# FIT_HDMI_X27-23.net
KiCad netlist of a schematic drawn in Altium Designer
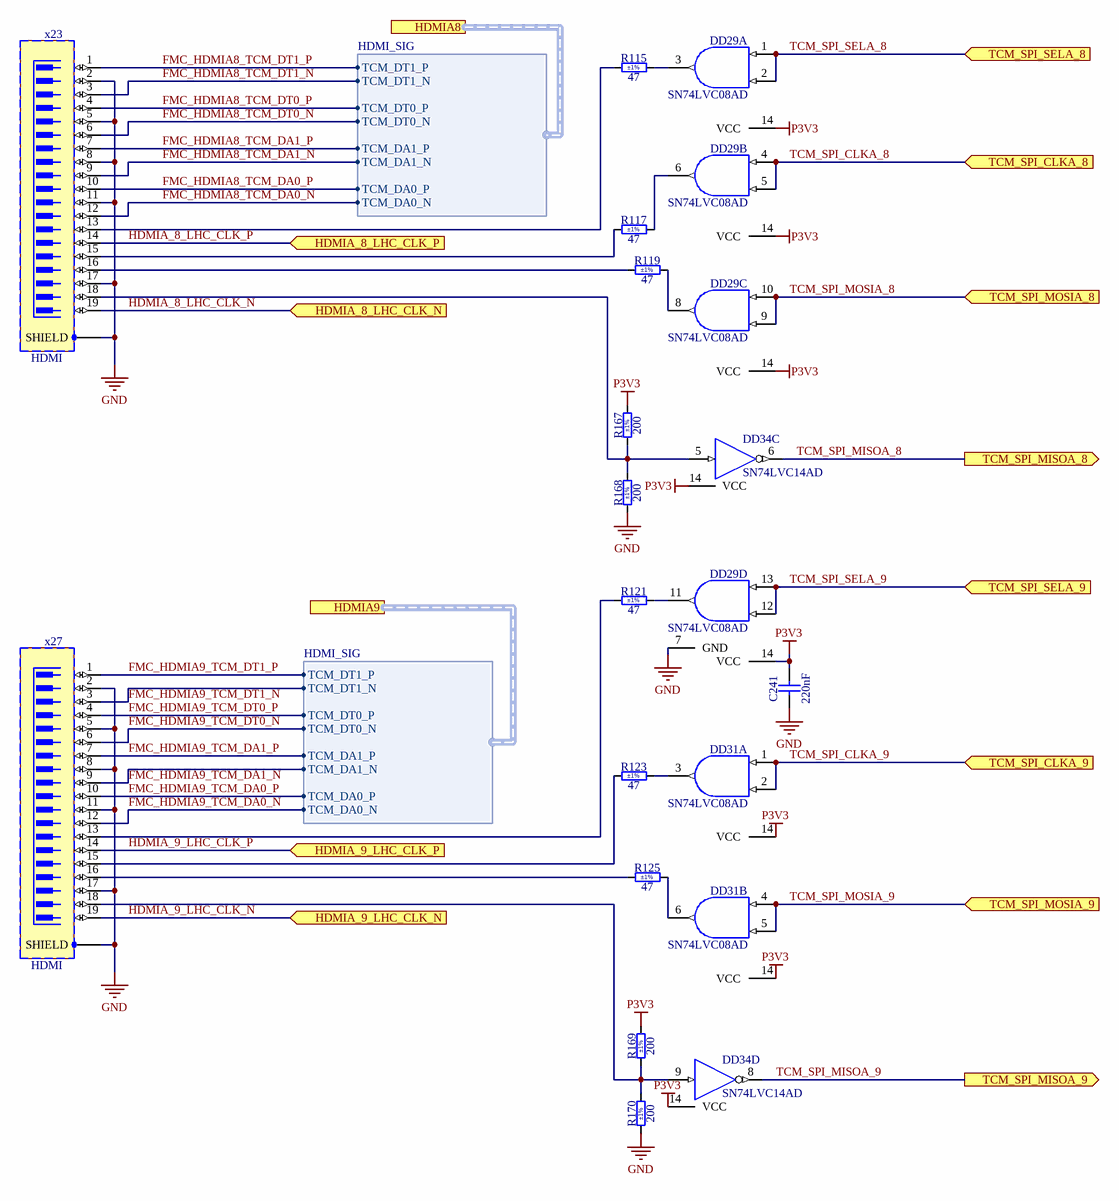
[diagram p0: FIT_HDMI_X27-23.SchDoc]

(export (version "E")
  (design (tool "Eeschema 10.0.6"))
  (components
    (comp (ref "C241")
      (value "220nF")
      (footprint "CAPC2012X135N")
      (description "Non-polarised capacitor")
      (fields
        (field (name "PART NUMBER") "CC0805_220NF_50V_10%_X7R")
        (field (name "VOLTAGE") "50V")
        (field (name "AUTHOR") "CERN DEM JLC")
      )
      (libsource (lib "Capacitors") (part "Capacitor - non polarized"))
    )
    (comp (ref "DD29")
      (value "SN74LVC08AD")
      (footprint "SOIC127P600X175-14N")
      (description "Quad 2-Input AND Gate")
      (fields (field (name "MANUFACTURER") "TEXAS INSTRUMENTS") (field (name "AUTHOR") "CERN DEM JLC"))
      (libsource (lib "ICs And Semiconductors") (part "7408"))
    )
    (comp (ref "DD31")
      (value "SN74LVC08AD")
      (footprint "SOIC127P600X175-14N")
      (description "Quad 2-Input AND Gate")
      (fields (field (name "MANUFACTURER") "TEXAS INSTRUMENTS") (field (name "AUTHOR") "CERN DEM JLC"))
      (libsource (lib "ICs And Semiconductors") (part "7408"))
    )
    (comp (ref "DD34")
      (value "SN74LVC14AD")
      (footprint "SOIC127P600X175-14N")
      (description "Hex Schmitt-Trigger Inverter")
      (fields (field (name "MANUFACTURER") "TEXAS INSTRUMENTS") (field (name "AUTHOR") "CERN DEM JMW"))
      (libsource (lib "ICs And Semiconductors") (part "7414"))
    )
    (comp (ref "R115")
      (value "47")
      (footprint "RESC2012X60N")
      (description "Resistor - 1%")
      (fields
        (field (name "TOLERANCE") "±1%")
        (field (name "PART NUMBER") "R0805_47R_1%_0.125W_100PPM")
        (field (name "POWER") "0.125W")
        (field (name "AUTHOR") "CERN DEM JLC")
      )
      (libsource (lib "Resistors") (part "Resistor - 1%"))
    )
    (comp (ref "R117")
      (value "47")
      (footprint "RESC2012X60N")
      (description "Resistor - 1%")
      (fields
        (field (name "TOLERANCE") "±1%")
        (field (name "PART NUMBER") "R0805_47R_1%_0.125W_100PPM")
        (field (name "POWER") "0.125W")
        (field (name "AUTHOR") "CERN DEM JLC")
      )
      (libsource (lib "Resistors") (part "Resistor - 1%"))
    )
    (comp (ref "R119")
      (value "47")
      (footprint "RESC2012X60N")
      (description "Resistor - 1%")
      (fields
        (field (name "TOLERANCE") "±1%")
        (field (name "PART NUMBER") "R0805_47R_1%_0.125W_100PPM")
        (field (name "POWER") "0.125W")
        (field (name "AUTHOR") "CERN DEM JLC")
      )
      (libsource (lib "Resistors") (part "Resistor - 1%"))
    )
    (comp (ref "R121")
      (value "47")
      (footprint "RESC2012X60N")
      (description "Resistor - 1%")
      (fields
        (field (name "TOLERANCE") "±1%")
        (field (name "PART NUMBER") "R0805_47R_1%_0.125W_100PPM")
        (field (name "POWER") "0.125W")
        (field (name "AUTHOR") "CERN DEM JLC")
      )
      (libsource (lib "Resistors") (part "Resistor - 1%"))
    )
    (comp (ref "R123")
      (value "47")
      (footprint "RESC2012X60N")
      (description "Resistor - 1%")
      (fields
        (field (name "TOLERANCE") "±1%")
        (field (name "PART NUMBER") "R0805_47R_1%_0.125W_100PPM")
        (field (name "POWER") "0.125W")
        (field (name "AUTHOR") "CERN DEM JLC")
      )
      (libsource (lib "Resistors") (part "Resistor - 1%"))
    )
    (comp (ref "R125")
      (value "47")
      (footprint "RESC2012X60N")
      (description "Resistor - 1%")
      (fields
        (field (name "TOLERANCE") "±1%")
        (field (name "PART NUMBER") "R0805_47R_1%_0.125W_100PPM")
        (field (name "POWER") "0.125W")
        (field (name "AUTHOR") "CERN DEM JLC")
      )
      (libsource (lib "Resistors") (part "Resistor - 1%"))
    )
    (comp (ref "R167")
      (value "200")
      (footprint "RESC2012X60N")
      (description "Resistor - 1%")
      (fields
        (field (name "TOLERANCE") "±1%")
        (field (name "PART NUMBER") "R0805_200R_1%_0.125W_100PPM")
        (field (name "POWER") "0.125W")
        (field (name "AUTHOR") "CERN DEM JLC")
      )
      (libsource (lib "Resistors") (part "Resistor - 1%"))
    )
    (comp (ref "R168")
      (value "200")
      (footprint "RESC2012X60N")
      (description "Resistor - 1%")
      (fields
        (field (name "TOLERANCE") "±1%")
        (field (name "PART NUMBER") "R0805_200R_1%_0.125W_100PPM")
        (field (name "POWER") "0.125W")
        (field (name "AUTHOR") "CERN DEM JLC")
      )
      (libsource (lib "Resistors") (part "Resistor - 1%"))
    )
    (comp (ref "R169")
      (value "200")
      (footprint "RESC2012X60N")
      (description "Resistor - 1%")
      (fields
        (field (name "TOLERANCE") "±1%")
        (field (name "PART NUMBER") "R0805_200R_1%_0.125W_100PPM")
        (field (name "POWER") "0.125W")
        (field (name "AUTHOR") "CERN DEM JLC")
      )
      (libsource (lib "Resistors") (part "Resistor - 1%"))
    )
    (comp (ref "R170")
      (value "200")
      (footprint "RESC2012X60N")
      (description "Resistor - 1%")
      (fields
        (field (name "TOLERANCE") "±1%")
        (field (name "PART NUMBER") "R0805_200R_1%_0.125W_100PPM")
        (field (name "POWER") "0.125W")
        (field (name "AUTHOR") "CERN DEM JLC")
      )
      (libsource (lib "Resistors") (part "Resistor - 1%"))
    )
    (comp (ref "x23")
      (value "HDMI")
      (footprint "TYCO_2007435-1")
      (description "Connector HDMI 19 Male + 1 Shield")
      (fields
        (field (name "PART NUMBER") "TYCO_2007435-1")
        (field (name "MANUFACTURER") "TYCO ELECTRONICS")
        (field (name "AUTHOR") "CERN DEM MR")
      )
      (libsource (lib "Connectors") (part "Connector HDMI 19 Male + 1 Shield"))
    )
    (comp (ref "x27")
      (value "HDMI")
      (footprint "TYCO_2007435-1")
      (description "Connector HDMI 19 Male + 1 Shield")
      (fields
        (field (name "PART NUMBER") "TYCO_2007435-1")
        (field (name "MANUFACTURER") "TYCO ELECTRONICS")
        (field (name "AUTHOR") "CERN DEM MR")
      )
      (libsource (lib "Connectors") (part "Connector HDMI 19 Male + 1 Shield"))
    )
  )
  (nets
    (net (code "2") (name "/FMC_HDMIA8_TCM_DA0_N") (class "Default")
      (node (ref "x23") (pin "12") (pinfunction "12_12") (pintype "bidirectional"))
    )
    (net (code "3") (name "/FMC_HDMIA8_TCM_DA0_P") (class "Default")
      (node (ref "x23") (pin "10") (pinfunction "10_10") (pintype "bidirectional"))
    )
    (net (code "4") (name "/FMC_HDMIA8_TCM_DA1_N") (class "Default")
      (node (ref "x23") (pin "9") (pinfunction "9_9") (pintype "bidirectional"))
    )
    (net (code "5") (name "/FMC_HDMIA8_TCM_DA1_P") (class "Default")
      (node (ref "x23") (pin "7") (pinfunction "7_7") (pintype "bidirectional"))
    )
    (net (code "6") (name "/FMC_HDMIA8_TCM_DT0_N") (class "Default")
      (node (ref "x23") (pin "6") (pinfunction "6_6") (pintype "bidirectional"))
    )
    (net (code "7") (name "/FMC_HDMIA8_TCM_DT0_P") (class "Default")
      (node (ref "x23") (pin "4") (pinfunction "4_4") (pintype "bidirectional"))
    )
    (net (code "8") (name "/FMC_HDMIA8_TCM_DT1_N") (class "Default")
      (node (ref "x23") (pin "3") (pinfunction "3_3") (pintype "bidirectional"))
    )
    (net (code "9") (name "/FMC_HDMIA8_TCM_DT1_P") (class "Default")
      (node (ref "x23") (pin "1") (pinfunction "1_1") (pintype "bidirectional"))
    )
    (net (code "10") (name "/FMC_HDMIA9_TCM_DA0_N") (class "Default")
      (node (ref "x27") (pin "12") (pinfunction "12_12") (pintype "bidirectional"))
    )
    (net (code "11") (name "/FMC_HDMIA9_TCM_DA0_P") (class "Default")
      (node (ref "x27") (pin "10") (pinfunction "10_10") (pintype "bidirectional"))
    )
    (net (code "12") (name "/FMC_HDMIA9_TCM_DA1_N") (class "Default")
      (node (ref "x27") (pin "9") (pinfunction "9_9") (pintype "bidirectional"))
    )
    (net (code "13") (name "/FMC_HDMIA9_TCM_DA1_P") (class "Default")
      (node (ref "x27") (pin "7") (pinfunction "7_7") (pintype "bidirectional"))
    )
    (net (code "14") (name "/FMC_HDMIA9_TCM_DT0_N") (class "Default")
      (node (ref "x27") (pin "6") (pinfunction "6_6") (pintype "bidirectional"))
    )
    (net (code "15") (name "/FMC_HDMIA9_TCM_DT0_P") (class "Default")
      (node (ref "x27") (pin "4") (pinfunction "4_4") (pintype "bidirectional"))
    )
    (net (code "16") (name "/FMC_HDMIA9_TCM_DT1_N") (class "Default")
      (node (ref "x27") (pin "3") (pinfunction "3_3") (pintype "bidirectional"))
    )
    (net (code "17") (name "/FMC_HDMIA9_TCM_DT1_P") (class "Default")
      (node (ref "x27") (pin "1") (pinfunction "1_1") (pintype "bidirectional"))
    )
    (net (code "18") (name "/HDMIA_8_LHC_CLK_N") (class "Default")
      (node (ref "x23") (pin "19") (pinfunction "19_19") (pintype "bidirectional"))
    )
    (net (code "19") (name "/HDMIA_8_LHC_CLK_P") (class "Default")
      (node (ref "x23") (pin "14") (pinfunction "14_14") (pintype "bidirectional"))
    )
    (net (code "20") (name "/HDMIA_9_LHC_CLK_N") (class "Default")
      (node (ref "x27") (pin "19") (pinfunction "19_19") (pintype "bidirectional"))
    )
    (net (code "21") (name "/HDMIA_9_LHC_CLK_P") (class "Default")
      (node (ref "x27") (pin "14") (pinfunction "14_14") (pintype "bidirectional"))
    )
    (net (code "22") (name "/TCM_SPI_CLKA_8") (class "Default")
      (node (ref "DD29") (pin "4") (pinfunction "A_4") (pintype "input"))
      (node (ref "DD29") (pin "5") (pinfunction "B_5") (pintype "input"))
    )
    (net (code "23") (name "/TCM_SPI_CLKA_9") (class "Default")
      (node (ref "DD31") (pin "1") (pinfunction "A_1") (pintype "input"))
      (node (ref "DD31") (pin "2") (pinfunction "B_2") (pintype "input"))
    )
    (net (code "24") (name "/TCM_SPI_MISOA_8") (class "Default")
      (node (ref "DD34") (pin "6") (pinfunction "OUT_6") (pintype "output"))
    )
    (net (code "25") (name "/TCM_SPI_MISOA_9") (class "Default")
      (node (ref "DD34") (pin "8") (pinfunction "OUT_8") (pintype "output"))
    )
    (net (code "26") (name "/TCM_SPI_MOSIA_8") (class "Default")
      (node (ref "DD29") (pin "10") (pinfunction "A_10") (pintype "input"))
      (node (ref "DD29") (pin "9") (pinfunction "B_9") (pintype "input"))
    )
    (net (code "27") (name "/TCM_SPI_MOSIA_9") (class "Default")
      (node (ref "DD31") (pin "4") (pinfunction "A_4") (pintype "input"))
      (node (ref "DD31") (pin "5") (pinfunction "B_5") (pintype "input"))
    )
    (net (code "28") (name "/TCM_SPI_SELA_8") (class "Default")
      (node (ref "DD29") (pin "1") (pinfunction "A_1") (pintype "input"))
      (node (ref "DD29") (pin "2") (pinfunction "B_2") (pintype "input"))
    )
    (net (code "29") (name "/TCM_SPI_SELA_9") (class "Default")
      (node (ref "DD29") (pin "12") (pinfunction "B_12") (pintype "input"))
      (node (ref "DD29") (pin "13") (pinfunction "A_13") (pintype "input"))
    )
    (net (code "31") (name "GND") (class "Default")
      (node (ref "C241") (pin "1") (pinfunction "1_1") (pintype "passive"))
      (node (ref "DD29") (pin "7") (pinfunction "GND_7") (pintype "power_in"))
      (node (ref "DD31") (pin "7") (pinfunction "GND_7") (pintype "power_in"))
      (node (ref "DD34") (pin "7") (pinfunction "GND_7") (pintype "power_in"))
      (node (ref "R168") (pin "1") (pinfunction "1_1") (pintype "passive"))
      (node (ref "R170") (pin "1") (pinfunction "1_1") (pintype "passive"))
      (node (ref "x23") (pin "11") (pinfunction "11_11") (pintype "bidirectional"))
      (node (ref "x23") (pin "17") (pinfunction "17_17") (pintype "bidirectional"))
      (node (ref "x23") (pin "2") (pinfunction "2_2") (pintype "bidirectional"))
      (node (ref "x23") (pin "5") (pinfunction "5_5") (pintype "bidirectional"))
      (node (ref "x23") (pin "8") (pinfunction "8_8") (pintype "bidirectional"))
      (node (ref "x23") (pin "SHIELD") (pinfunction "SHIELD_SHIELD") (pintype "power_in"))
      (node (ref "x27") (pin "11") (pinfunction "11_11") (pintype "bidirectional"))
      (node (ref "x27") (pin "17") (pinfunction "17_17") (pintype "bidirectional"))
      (node (ref "x27") (pin "2") (pinfunction "2_2") (pintype "bidirectional"))
      (node (ref "x27") (pin "5") (pinfunction "5_5") (pintype "bidirectional"))
      (node (ref "x27") (pin "8") (pinfunction "8_8") (pintype "bidirectional"))
      (node (ref "x27") (pin "SHIELD") (pinfunction "SHIELD_SHIELD") (pintype "power_in"))
    )
    (net (code "32") (name "Net-(DD29A-Y)") (class "Default")
      (node (ref "DD29") (pin "3") (pinfunction "Y_3") (pintype "output"))
      (node (ref "R115") (pin "2") (pinfunction "2_2") (pintype "passive"))
    )
    (net (code "33") (name "Net-(DD29B-Y)") (class "Default")
      (node (ref "DD29") (pin "6") (pinfunction "Y_6") (pintype "output"))
      (node (ref "R117") (pin "2") (pinfunction "2_2") (pintype "passive"))
    )
    (net (code "34") (name "Net-(DD29C-Y)") (class "Default")
      (node (ref "DD29") (pin "8") (pinfunction "Y_8") (pintype "output"))
      (node (ref "R119") (pin "2") (pinfunction "2_2") (pintype "passive"))
    )
    (net (code "35") (name "Net-(DD29D-Y)") (class "Default")
      (node (ref "DD29") (pin "11") (pinfunction "Y_11") (pintype "output"))
      (node (ref "R121") (pin "2") (pinfunction "2_2") (pintype "passive"))
    )
    (net (code "36") (name "Net-(DD31A-Y)") (class "Default")
      (node (ref "DD31") (pin "3") (pinfunction "Y_3") (pintype "output"))
      (node (ref "R123") (pin "2") (pinfunction "2_2") (pintype "passive"))
    )
    (net (code "37") (name "Net-(DD31B-Y)") (class "Default")
      (node (ref "DD31") (pin "6") (pinfunction "Y_6") (pintype "output"))
      (node (ref "R125") (pin "2") (pinfunction "2_2") (pintype "passive"))
    )
    (net (code "38") (name "Net-(DD34C-IN)") (class "Default")
      (node (ref "DD34") (pin "5") (pinfunction "IN_5") (pintype "input"))
      (node (ref "R167") (pin "1") (pinfunction "1_1") (pintype "passive"))
      (node (ref "R168") (pin "2") (pinfunction "2_2") (pintype "passive"))
      (node (ref "x23") (pin "18") (pinfunction "18_18") (pintype "bidirectional"))
    )
    (net (code "39") (name "Net-(DD34D-IN)") (class "Default")
      (node (ref "DD34") (pin "9") (pinfunction "IN_9") (pintype "input"))
      (node (ref "R169") (pin "1") (pinfunction "1_1") (pintype "passive"))
      (node (ref "R170") (pin "2") (pinfunction "2_2") (pintype "passive"))
      (node (ref "x27") (pin "18") (pinfunction "18_18") (pintype "bidirectional"))
    )
    (net (code "40") (name "Net-(R115-Pad1)") (class "Default")
      (node (ref "R115") (pin "1") (pinfunction "1_1") (pintype "passive"))
      (node (ref "x23") (pin "13") (pinfunction "13_13") (pintype "bidirectional"))
    )
    (net (code "41") (name "Net-(R117-Pad1)") (class "Default")
      (node (ref "R117") (pin "1") (pinfunction "1_1") (pintype "passive"))
      (node (ref "x23") (pin "15") (pinfunction "15_15") (pintype "bidirectional"))
    )
    (net (code "42") (name "Net-(R119-Pad1)") (class "Default")
      (node (ref "R119") (pin "1") (pinfunction "1_1") (pintype "passive"))
      (node (ref "x23") (pin "16") (pinfunction "16_16") (pintype "bidirectional"))
    )
    (net (code "43") (name "Net-(R121-Pad1)") (class "Default")
      (node (ref "R121") (pin "1") (pinfunction "1_1") (pintype "passive"))
      (node (ref "x27") (pin "13") (pinfunction "13_13") (pintype "bidirectional"))
    )
    (net (code "44") (name "Net-(R123-Pad1)") (class "Default")
      (node (ref "R123") (pin "1") (pinfunction "1_1") (pintype "passive"))
      (node (ref "x27") (pin "15") (pinfunction "15_15") (pintype "bidirectional"))
    )
    (net (code "45") (name "Net-(R125-Pad1)") (class "Default")
      (node (ref "R125") (pin "1") (pinfunction "1_1") (pintype "passive"))
      (node (ref "x27") (pin "16") (pinfunction "16_16") (pintype "bidirectional"))
    )
    (net (code "46") (name "P3V3") (class "Default")
      (node (ref "C241") (pin "2") (pinfunction "2_2") (pintype "passive"))
      (node (ref "DD29") (pin "14") (pinfunction "VCC_14") (pintype "power_in"))
      (node (ref "DD31") (pin "14") (pinfunction "VCC_14") (pintype "power_in"))
      (node (ref "DD34") (pin "14") (pinfunction "VCC_14") (pintype "power_in"))
      (node (ref "R167") (pin "2") (pinfunction "2_2") (pintype "passive"))
      (node (ref "R169") (pin "2") (pinfunction "2_2") (pintype "passive"))
    )
  )
)
